# BoardB-Power.net
KiCad netlist of a schematic drawn in Altium Designer
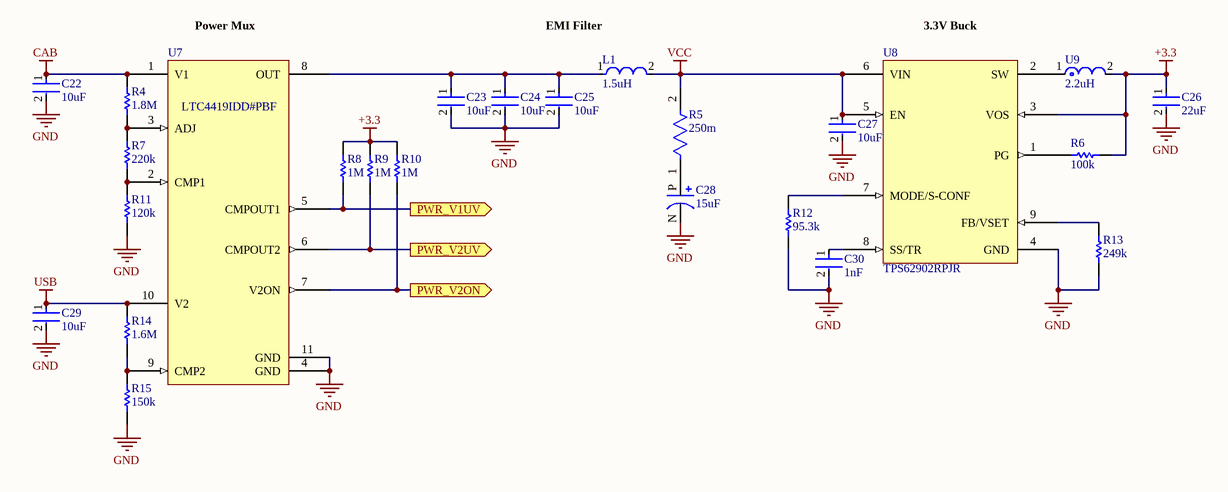
[diagram p0: BoardB-Power.SchDoc]

(export (version "E")
  (design (tool "Eeschema 10.0.6"))
  (components
    (comp (ref "C22")
      (value "10uF")
      (footprint "FP-GRM21B-0_15-IPC_C")
      (description "Chip Multilayer Ceramic Capacitors for General Purpose, 0805, 10uF, X5R, 15%, 10%, 25V")
      (fields (field (name "VOLTAGE") "25V") (field (name "TOLERANCE") "10%"))
      (libsource (lib "Altium Content Vault") (part "b4654b650e69147ec39a6b967a45e02"))
    )
    (comp (ref "C23")
      (value "10uF")
      (footprint "FP-GRM21B-0_15-IPC_C")
      (description "Chip Multilayer Ceramic Capacitors for General Purpose, 0805, 10uF, X5R, 15%, 10%, 25V")
      (fields (field (name "VOLTAGE") "25V") (field (name "TOLERANCE") "10%"))
      (libsource (lib "Altium Content Vault") (part "b4654b650e69147ec39a6b967a45e02"))
    )
    (comp (ref "C24")
      (value "10uF")
      (footprint "FP-GRM21B-0_15-IPC_C")
      (description "Chip Multilayer Ceramic Capacitors for General Purpose, 0805, 10uF, X5R, 15%, 10%, 25V")
      (fields (field (name "VOLTAGE") "25V") (field (name "TOLERANCE") "10%"))
      (libsource (lib "Altium Content Vault") (part "b4654b650e69147ec39a6b967a45e02"))
    )
    (comp (ref "C25")
      (value "10uF")
      (footprint "FP-GRM21B-0_15-IPC_C")
      (description "Chip Multilayer Ceramic Capacitors for General Purpose, 0805, 10uF, X5R, 15%, 10%, 25V")
      (fields (field (name "VOLTAGE") "25V") (field (name "TOLERANCE") "10%"))
      (libsource (lib "Altium Content Vault") (part "b4654b650e69147ec39a6b967a45e02"))
    )
    (comp (ref "C26")
      (value "22uF")
      (footprint "FP-CL21-IPC_C")
      (description "CL21 Series 0805 22uF 16V ±20% Tolerance X5R Multilayer Ceramic Chip Capacitor")
      (fields (field (name "TOLERANCE") "20%"))
      (libsource (lib "Altium Content Vault") (part "b4654b650e69147ec39a6b967a45e02"))
    )
    (comp (ref "C27")
      (value "10uF")
      (footprint "FP-GRM21B-0_15-IPC_C")
      (description "Chip Multilayer Ceramic Capacitors for General Purpose, 0805, 10uF, X5R, 15%, 10%, 25V")
      (fields (field (name "VOLTAGE") "25V") (field (name "TOLERANCE") "10%"))
      (libsource (lib "Altium Content Vault") (part "b4654b650e69147ec39a6b967a45e02"))
    )
    (comp (ref "C28")
      (value "15uF")
      (footprint "16TQC15M")
      (description "Polymer capacitor 15 uF 16 VDC, 16TQC15M, Panasonic Automotive & Industrial Systems")
      (fields (field (name "TOLERANCE") "20%") (field (name "VOLTAGE") "16V"))
      (libsource (lib "BoardB") (part "16TQC15M"))
    )
    (comp (ref "C29")
      (value "10uF")
      (footprint "FP-GRM21B-0_15-IPC_C")
      (description "Chip Multilayer Ceramic Capacitors for General Purpose, 0805, 10uF, X5R, 15%, 10%, 25V")
      (fields (field (name "VOLTAGE") "25V") (field (name "TOLERANCE") "10%"))
      (libsource (lib "Altium Content Vault") (part "b4654b650e69147ec39a6b967a45e02"))
    )
    (comp (ref "C30")
      (value "1nF")
      (footprint "FP-CL957-IPC_C")
      (description "Cap Ceramic 1nF 50V X7R ±10% SMD 0402 +125°C Paper T/R")
      (fields (field (name "TOLERANCE") "10%") (field (name "VOLTAGE") "50V"))
      (libsource (lib "Altium Content Vault") (part "b4654b650e69147ec39a6b967a45e02"))
    )
    (comp (ref "L1")
      (value "1.5uH")
      (footprint "FP-DFE252010C-IPC_C")
      (description "Shielded Wirewound Inductor 1.5uH  1900mA 0.108Ω 1008 (2520)")
      (fields (field (name "TOLERANCE") "20%"))
      (libsource (lib "Altium Content Vault") (part "725321dda6339637d4d059423bc1c3c"))
    )
    (comp (ref "R4")
      (value "1.8M")
      (footprint "RESC2013X70X40NL20T20")
      (fields (field (name "MANUFACTURER") "Panasonic") (field (name "PART NUMBER") "ERJ-6ENF1804V"))
      (libsource (lib "Altium Content Vault") (part "RES"))
    )
    (comp (ref "R5")
      (value "250m")
      (footprint "FP-CSR1206-IPC_A")
      (description "General Purpose Thick Film Chip Resistor, 1206, 0.25Ω, 1%, 100ppm/°C, 0.5W")
      (fields (field (name "TOLERANCE") "1%"))
      (libsource (lib "Altium Content Vault") (part "1029c3af85768c4190bb7ad29bc67b5"))
    )
    (comp (ref "R6")
      (value "100k")
      (footprint "RESC1005X40X25NL05T10")
      (fields (field (name "PART NUMBER") "RC0402FR-07100KL") (field (name "MANUFACTURER") "Yageo / Phycomp"))
      (libsource (lib "Altium Content Vault") (part "RES"))
    )
    (comp (ref "R7")
      (value "220k")
      (footprint "RESC1005X40X25ML05T05")
      (fields (field (name "MANUFACTURER") "Panasonic") (field (name "PART NUMBER") "ERJ2RKF2203X"))
      (libsource (lib "Altium Content Vault") (part "RES"))
    )
    (comp (ref "R8")
      (value "1M")
      (footprint "RESC0603X28X15NL05T05")
      (fields (field (name "PART NUMBER") "CRCW02011M00FKED") (field (name "MANUFACTURER") "Vishay Dale"))
      (libsource (lib "Altium Content Vault") (part "RES"))
    )
    (comp (ref "R9")
      (value "1M")
      (footprint "RESC0603X28X15NL05T05")
      (fields (field (name "PART NUMBER") "CRCW02011M00FKED") (field (name "MANUFACTURER") "Vishay Dale"))
      (libsource (lib "Altium Content Vault") (part "RES"))
    )
    (comp (ref "R10")
      (value "1M")
      (footprint "RESC0603X28X15NL05T05")
      (fields (field (name "PART NUMBER") "CRCW02011M00FKED") (field (name "MANUFACTURER") "Vishay Dale"))
      (libsource (lib "Altium Content Vault") (part "RES"))
    )
    (comp (ref "R11")
      (value "120k")
      (footprint "RESC1608X55X25NL10T15")
      (description "Chip Resistor, 120 KOhm, +/- 1%, 100 mW, -55 to 155 degC, 0603 (1608 Metric), RoHS, Tape and Reel")
      (fields (field (name "TOLERANCE") "10%"))
      (libsource (lib "Altium Content Vault") (part "RES-2"))
    )
    (comp (ref "R12")
      (value "95.3k")
      (footprint "RESC1005X40X25NL05T10")
      (fields (field (name "PART NUMBER") "RC0402FR-0795K3L") (field (name "MANUFACTURER") "Yageo / Phycomp"))
      (libsource (lib "Altium Content Vault") (part "RES"))
    )
    (comp (ref "R13")
      (value "249k")
      (footprint "RESC1005X40X25NL05T05")
      (fields (field (name "MANUFACTURER") "Panasonic") (field (name "PART NUMBER") "ERJ-2RKF2493X"))
      (libsource (lib "Altium Content Vault") (part "RES"))
    )
    (comp (ref "R14")
      (value "1.6M")
      (footprint "RESC3216X70X50LL05T20")
      (fields (field (name "PART NUMBER") "ERJ-8ENF1604V") (field (name "MANUFACTURER") "Panasonic"))
      (libsource (lib "Altium Content Vault") (part "RES"))
    )
    (comp (ref "R15")
      (value "150k")
      (footprint "RESC1005X40X25NL05T10")
      (fields (field (name "PART NUMBER") "RC0402FR-07150KL") (field (name "MANUFACTURER") "Yageo / Phycomp"))
      (libsource (lib "Altium Content Vault") (part "RES"))
    )
    (comp (ref "U7")
      (value "LTC4419IDD#PBF")
      (footprint "LTC4419IDD#PBF")
      (description "IC SOURCE SELECTOR SWITCH 10DFN")
      (fields (field (name "MANUFACTURER") "Analog Devices / Linear Technology"))
      (libsource (lib "BoardB") (part "LTC4419IDD#PBF"))
    )
    (comp (ref "U8")
      (value "TPS62902RPJR")
      (footprint "TPS62902RPJR")
      (fields (field (name "MANUFACTURER") "Texas Instruments"))
      (libsource (lib "BoardB") (part "TPS62902RPJR"))
    )
    (comp (ref "U9")
      (value "2.2uH")
      (footprint "FP-FDSD0420-MFG")
      (description "FIXED IND 2.2UH 3.6A 47 MOHM SMD")
      (fields (field (name "TOLERANCE") "20%"))
      (libsource (lib "Altium Content Vault") (part "4cc4b267dca4c8e51f7102f422741d8"))
    )
  )
  (nets
    (net (code "1") (name "+3.3") (class "Default")
      (node (ref "C26") (pin "1") (pinfunction "1_1") (pintype "passive"))
      (node (ref "R10") (pin "2") (pinfunction "2_2") (pintype "passive"))
      (node (ref "R6") (pin "2") (pinfunction "2_2") (pintype "passive"))
      (node (ref "R8") (pin "2") (pinfunction "2_2") (pintype "passive"))
      (node (ref "R9") (pin "2") (pinfunction "2_2") (pintype "passive"))
      (node (ref "U8") (pin "3") (pinfunction "VOS_3") (pintype "input"))
      (node (ref "U9") (pin "2") (pinfunction "2_2") (pintype "passive"))
    )
    (net (code "2") (name "/PWR_V1UV") (class "Default")
      (node (ref "R8") (pin "1") (pinfunction "1_1") (pintype "passive"))
      (node (ref "U7") (pin "5") (pinfunction "CMPOUT1_5") (pintype "output"))
    )
    (net (code "3") (name "/PWR_V2ON") (class "Default")
      (node (ref "R10") (pin "1") (pinfunction "1_1") (pintype "passive"))
      (node (ref "U7") (pin "7") (pinfunction "V2ON_7") (pintype "output"))
    )
    (net (code "4") (name "/PWR_V2UV") (class "Default")
      (node (ref "R9") (pin "1") (pinfunction "1_1") (pintype "passive"))
      (node (ref "U7") (pin "6") (pinfunction "CMPOUT2_6") (pintype "output"))
    )
    (net (code "5") (name "CAB") (class "Default")
      (node (ref "C22") (pin "1") (pinfunction "1_1") (pintype "passive"))
      (node (ref "R4") (pin "2") (pinfunction "2_2") (pintype "passive"))
      (node (ref "U7") (pin "1") (pinfunction "V1_1") (pintype "power_in"))
    )
    (net (code "6") (name "GND") (class "Default")
      (node (ref "C22") (pin "2") (pinfunction "2_2") (pintype "passive"))
      (node (ref "C23") (pin "2") (pinfunction "2_2") (pintype "passive"))
      (node (ref "C24") (pin "2") (pinfunction "2_2") (pintype "passive"))
      (node (ref "C25") (pin "2") (pinfunction "2_2") (pintype "passive"))
      (node (ref "C26") (pin "2") (pinfunction "2_2") (pintype "passive"))
      (node (ref "C27") (pin "2") (pinfunction "2_2") (pintype "passive"))
      (node (ref "C28") (pin "N") (pintype "passive"))
      (node (ref "C29") (pin "2") (pinfunction "2_2") (pintype "passive"))
      (node (ref "C30") (pin "2") (pinfunction "2_2") (pintype "passive"))
      (node (ref "R11") (pin "2") (pinfunction "2_2") (pintype "passive"))
      (node (ref "R12") (pin "1") (pinfunction "1_1") (pintype "passive"))
      (node (ref "R13") (pin "2") (pinfunction "2_2") (pintype "passive"))
      (node (ref "R15") (pin "1") (pinfunction "1_1") (pintype "passive"))
      (node (ref "U7") (pin "11") (pinfunction "GND_11") (pintype "power_in"))
      (node (ref "U7") (pin "4") (pinfunction "GND_4") (pintype "power_in"))
      (node (ref "U8") (pin "4") (pinfunction "GND_4") (pintype "power_in"))
    )
    (net (code "7") (name "Net-(C28-PadP)") (class "Default")
      (node (ref "C28") (pin "P") (pintype "passive"))
      (node (ref "R5") (pin "1") (pinfunction "1_1") (pintype "passive"))
    )
    (net (code "8") (name "Net-(U7-ADJ)") (class "Default")
      (node (ref "R4") (pin "1") (pinfunction "1_1") (pintype "passive"))
      (node (ref "R7") (pin "2") (pinfunction "2_2") (pintype "passive"))
      (node (ref "U7") (pin "3") (pinfunction "ADJ_3") (pintype "input"))
    )
    (net (code "9") (name "Net-(U7-CMP1)") (class "Default")
      (node (ref "R11") (pin "1") (pinfunction "1_1") (pintype "passive"))
      (node (ref "R7") (pin "1") (pinfunction "1_1") (pintype "passive"))
      (node (ref "U7") (pin "2") (pinfunction "CMP1_2") (pintype "input"))
    )
    (net (code "10") (name "Net-(U7-CMP2)") (class "Default")
      (node (ref "R14") (pin "1") (pinfunction "1_1") (pintype "passive"))
      (node (ref "R15") (pin "2") (pinfunction "2_2") (pintype "passive"))
      (node (ref "U7") (pin "9") (pinfunction "CMP2_9") (pintype "input"))
    )
    (net (code "11") (name "Net-(U7-OUT)") (class "Default")
      (node (ref "C23") (pin "1") (pinfunction "1_1") (pintype "passive"))
      (node (ref "C24") (pin "1") (pinfunction "1_1") (pintype "passive"))
      (node (ref "C25") (pin "1") (pinfunction "1_1") (pintype "passive"))
      (node (ref "L1") (pin "1") (pinfunction "1_1") (pintype "passive"))
      (node (ref "U7") (pin "8") (pinfunction "OUT_8") (pintype "power_in"))
    )
    (net (code "12") (name "Net-(U8-FB{slash}VSET)") (class "Default")
      (node (ref "R13") (pin "1") (pinfunction "1_1") (pintype "passive"))
      (node (ref "U8") (pin "9") (pinfunction "FB/VSET_9") (pintype "input"))
    )
    (net (code "13") (name "Net-(U8-MODE{slash}S-CONF)") (class "Default")
      (node (ref "R12") (pin "2") (pinfunction "2_2") (pintype "passive"))
      (node (ref "U8") (pin "7") (pinfunction "MODE/S-CONF_7") (pintype "input"))
    )
    (net (code "14") (name "Net-(U8-PG)") (class "Default")
      (node (ref "R6") (pin "1") (pinfunction "1_1") (pintype "passive"))
      (node (ref "U8") (pin "1") (pinfunction "PG_1") (pintype "output"))
    )
    (net (code "15") (name "Net-(U8-SS{slash}TR)") (class "Default")
      (node (ref "C30") (pin "1") (pinfunction "1_1") (pintype "passive"))
      (node (ref "U8") (pin "8") (pinfunction "SS/TR_8") (pintype "input"))
    )
    (net (code "16") (name "Net-(U8-SW)") (class "Default")
      (node (ref "U8") (pin "2") (pinfunction "SW_2") (pintype "power_in"))
      (node (ref "U9") (pin "1") (pinfunction "1_1") (pintype "passive"))
    )
    (net (code "17") (name "USB") (class "Default")
      (node (ref "C29") (pin "1") (pinfunction "1_1") (pintype "passive"))
      (node (ref "R14") (pin "2") (pinfunction "2_2") (pintype "passive"))
      (node (ref "U7") (pin "10") (pinfunction "V2_10") (pintype "power_in"))
    )
    (net (code "18") (name "VCC") (class "Default")
      (node (ref "C27") (pin "1") (pinfunction "1_1") (pintype "passive"))
      (node (ref "L1") (pin "2") (pinfunction "2_2") (pintype "passive"))
      (node (ref "R5") (pin "2") (pinfunction "2_2") (pintype "passive"))
      (node (ref "U8") (pin "5") (pinfunction "EN_5") (pintype "input"))
      (node (ref "U8") (pin "6") (pinfunction "VIN_6") (pintype "power_in"))
    )
  )
)
